# singleboard.net
KiCad netlist of a schematic drawn in EAGLE
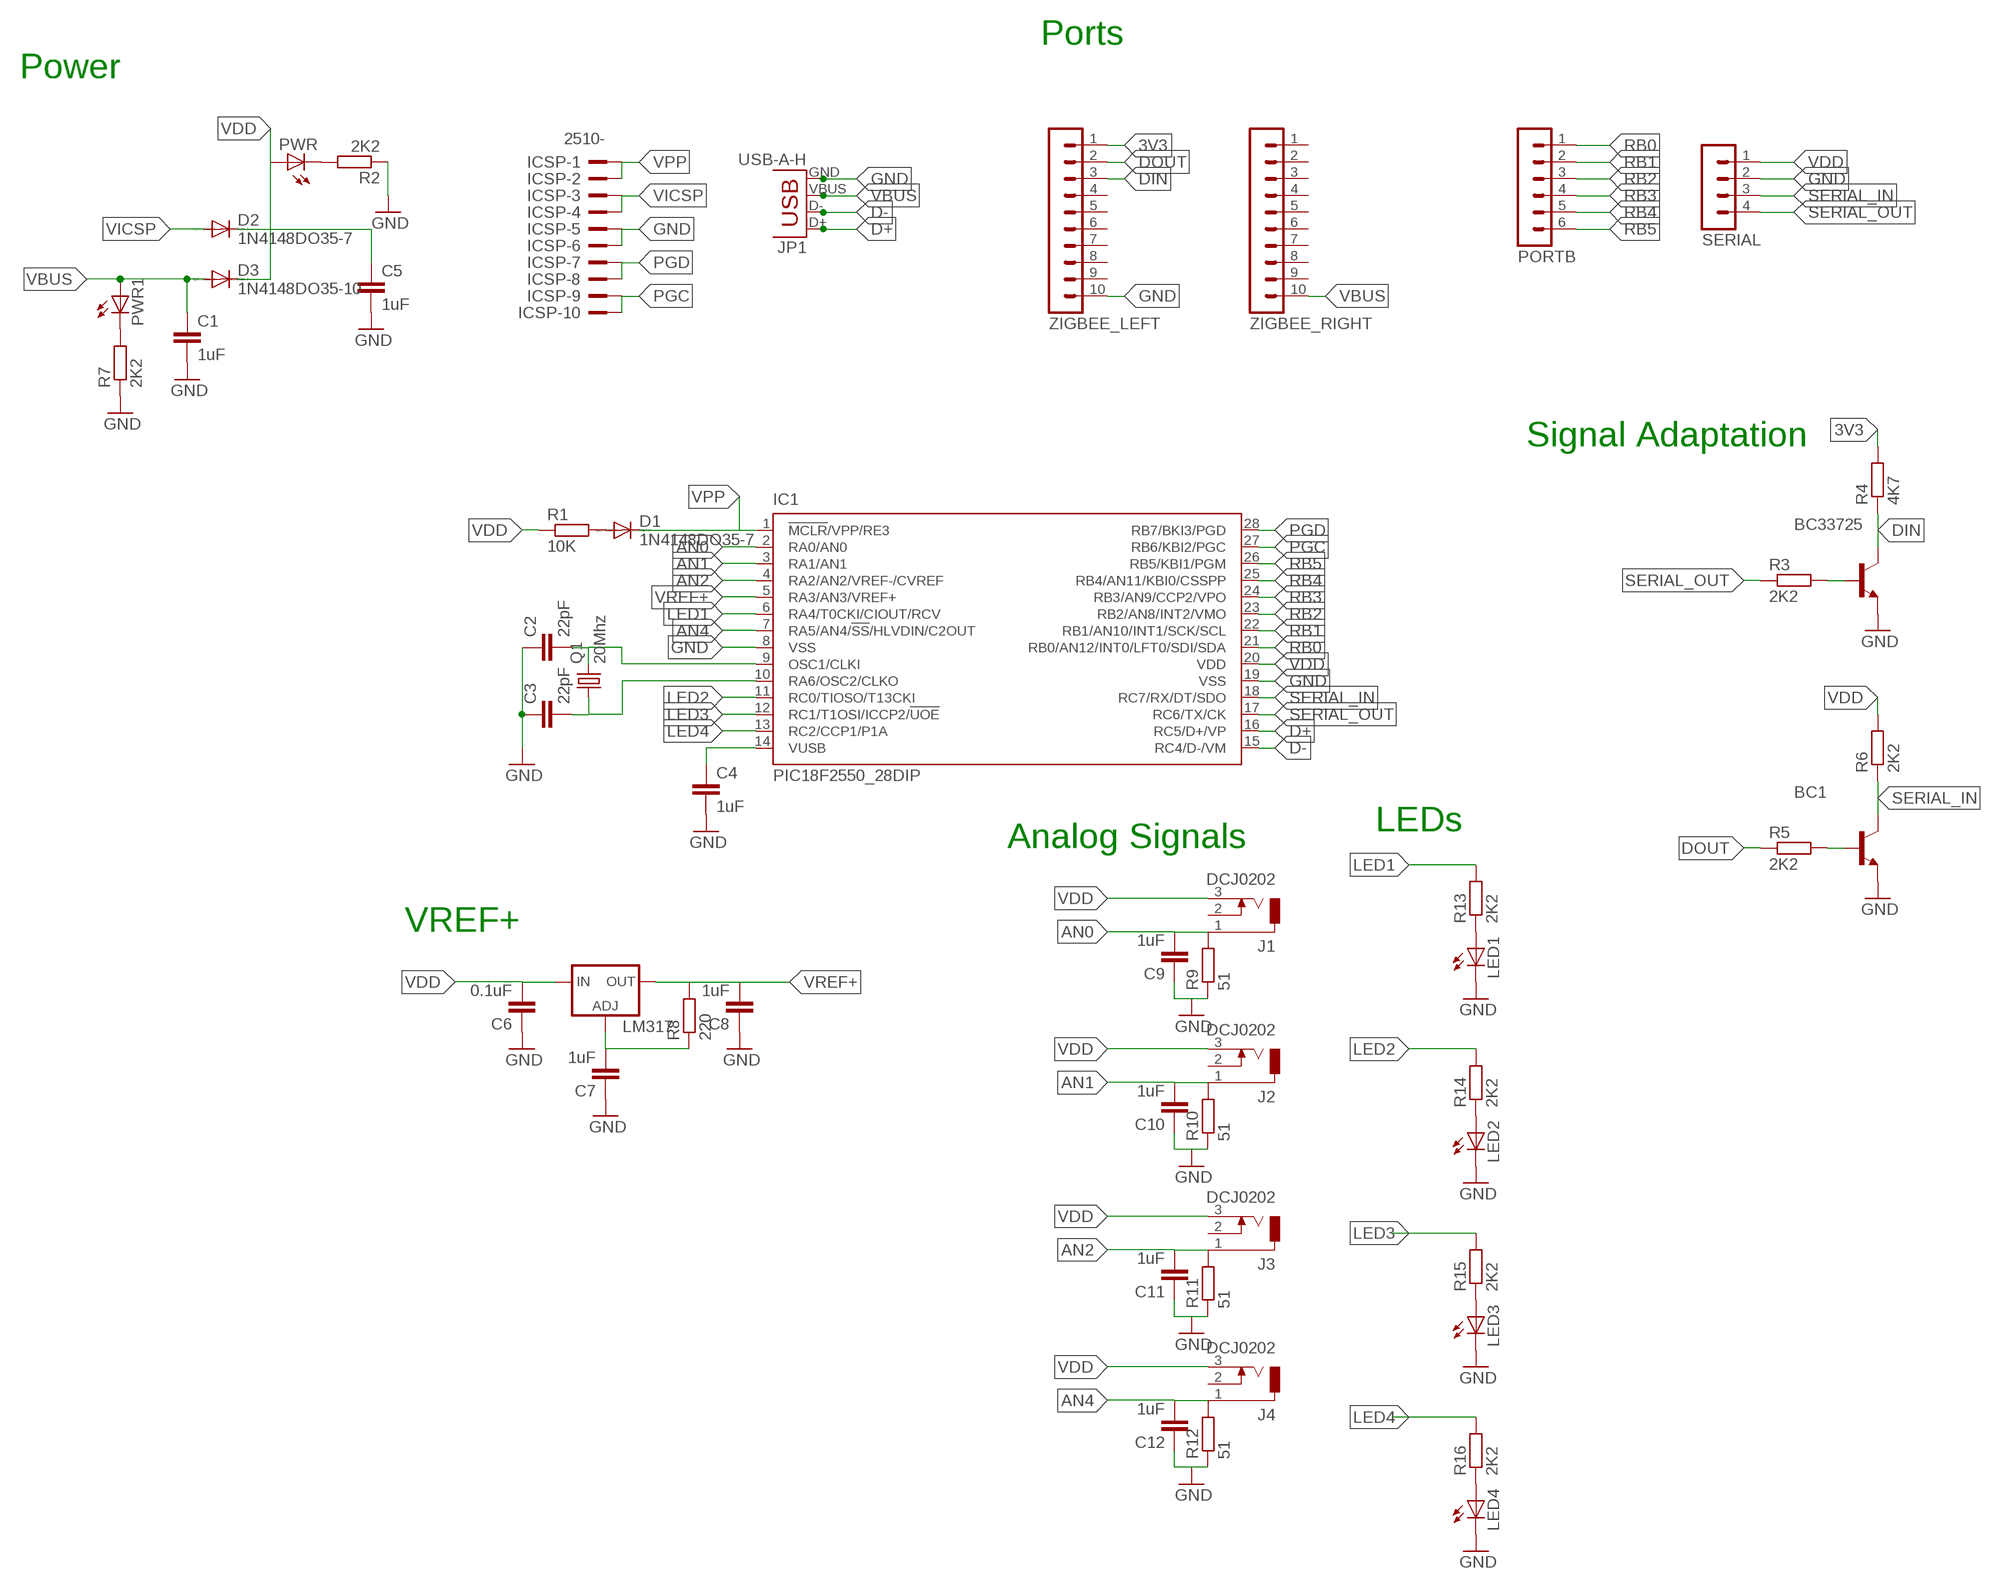
[diagram p0: schematic, sheet 1]

(export (version "E")
  (design (tool "Eeschema 10.0.6"))
  (components
    (comp (ref "BC1")
      (value "BC337-25-NPN-TO92-CBE")
      (footprint "eagle-import:TO92-CBE")
      (libsource (lib "eagle-import") (part "-NPN-TO92-CBEBC337-25"))
    )
    (comp (ref "BC33725")
      (value "BC337-25-NPN-TO92-CBE")
      (footprint "eagle-import:TO92-CBE")
      (libsource (lib "eagle-import") (part "-NPN-TO92-CBEBC337-25"))
    )
    (comp (ref "C1")
      (value "1uF")
      (footprint "eagle-import:C050-025X075")
      (libsource (lib "eagle-import") (part "C-EU050-025X075"))
    )
    (comp (ref "C2")
      (value "22pF")
      (footprint "eagle-import:C025-024X044")
      (libsource (lib "eagle-import") (part "C-EU025-024X044"))
    )
    (comp (ref "C3")
      (value "22pF")
      (footprint "eagle-import:C025-024X044")
      (libsource (lib "eagle-import") (part "C-EU025-024X044"))
    )
    (comp (ref "C4")
      (value "1uF")
      (footprint "eagle-import:C025-024X044")
      (libsource (lib "eagle-import") (part "C-EU025-024X044"))
    )
    (comp (ref "C5")
      (value "1uF")
      (footprint "eagle-import:C025-024X044")
      (libsource (lib "eagle-import") (part "C-EU025-024X044"))
    )
    (comp (ref "C6")
      (value "0.1uF")
      (footprint "eagle-import:C050-025X075")
      (libsource (lib "eagle-import") (part "C-EU050-025X075"))
    )
    (comp (ref "C7")
      (value "1uF")
      (footprint "eagle-import:C050-025X075")
      (libsource (lib "eagle-import") (part "C-EU050-025X075"))
    )
    (comp (ref "C8")
      (value "1uF")
      (footprint "eagle-import:C050-025X075")
      (libsource (lib "eagle-import") (part "C-EU050-025X075"))
    )
    (comp (ref "C9")
      (value "1uF")
      (footprint "eagle-import:C050-025X075")
      (libsource (lib "eagle-import") (part "C-EU050-025X075"))
    )
    (comp (ref "C10")
      (value "1uF")
      (footprint "eagle-import:C050-025X075")
      (libsource (lib "eagle-import") (part "C-EU050-025X075"))
    )
    (comp (ref "C11")
      (value "1uF")
      (footprint "eagle-import:C050-025X075")
      (libsource (lib "eagle-import") (part "C-EU050-025X075"))
    )
    (comp (ref "C12")
      (value "1uF")
      (footprint "eagle-import:C050-025X075")
      (libsource (lib "eagle-import") (part "C-EU050-025X075"))
    )
    (comp (ref "D1")
      (value "1N4148DO35-7")
      (footprint "eagle-import:DO35-7")
      (libsource (lib "eagle-import") (part "1N4148DO35-7"))
    )
    (comp (ref "D2")
      (value "1N4148DO35-7")
      (footprint "eagle-import:DO35-7")
      (libsource (lib "eagle-import") (part "1N4148DO35-7"))
    )
    (comp (ref "D3")
      (value "1N4148DO35-10")
      (footprint "eagle-import:DO35-10")
      (libsource (lib "eagle-import") (part "1N4148DO35-10"))
    )
    (comp (ref "IC1")
      (value "PIC18F2550_28DIP")
      (footprint "eagle-import:DIL28-3")
      (fields (field (name "MF") "MICROCHIP") (field (name "MPN") "PIC18F2550-I/SP"))
      (libsource (lib "eagle-import") (part "PIC18F2_28DIP550"))
    )
    (comp (ref "ICSP")
      (value "2510-")
      (footprint "eagle-import:PAK100_2500-10")
      (fields (field (name "MF") "3M") (field (name "MPN") "2510-6002UB"))
      (libsource (lib "eagle-import") (part "2510-"))
    )
    (comp (ref "J1")
      (value "DCJ0202")
      (footprint "eagle-import:DCJ0202")
      (libsource (lib "eagle-import") (part "DCJ0202"))
    )
    (comp (ref "J2")
      (value "DCJ0202")
      (footprint "eagle-import:DCJ0202")
      (libsource (lib "eagle-import") (part "DCJ0202"))
    )
    (comp (ref "J3")
      (value "DCJ0202")
      (footprint "eagle-import:DCJ0202")
      (libsource (lib "eagle-import") (part "DCJ0202"))
    )
    (comp (ref "J4")
      (value "DCJ0202")
      (footprint "eagle-import:DCJ0202")
      (libsource (lib "eagle-import") (part "DCJ0202"))
    )
    (comp (ref "JP1")
      (value "USB-A-H")
      (footprint "eagle-import:USB-A-H")
      (libsource (lib "eagle-import") (part "USB-A-H"))
    )
    (comp (ref "LED1")
      (value "LED3MM")
      (footprint "eagle-import:LED3MM")
      (libsource (lib "eagle-import") (part "LED3MM"))
    )
    (comp (ref "LED2")
      (value "LED3MM")
      (footprint "eagle-import:LED3MM")
      (libsource (lib "eagle-import") (part "LED3MM"))
    )
    (comp (ref "LED3")
      (value "LED3MM")
      (footprint "eagle-import:LED3MM")
      (libsource (lib "eagle-import") (part "LED3MM"))
    )
    (comp (ref "LED4")
      (value "LED3MM")
      (footprint "eagle-import:LED3MM")
      (libsource (lib "eagle-import") (part "LED3MM"))
    )
    (comp (ref "LM317")
      (value "LM317TS")
      (footprint "eagle-import:317TS")
      (libsource (lib "eagle-import") (part "LM317TS"))
    )
    (comp (ref "PORTB")
      (value "MA06-1")
      (footprint "eagle-import:MA06-1")
      (libsource (lib "eagle-import") (part "MA06-1"))
    )
    (comp (ref "PWR")
      (value "LED3MM")
      (footprint "eagle-import:LED3MM")
      (libsource (lib "eagle-import") (part "LED3MM"))
    )
    (comp (ref "PWR1")
      (value "LED3MM")
      (footprint "eagle-import:LED3MM")
      (libsource (lib "eagle-import") (part "LED3MM"))
    )
    (comp (ref "Q1")
      (value "20Mhz")
      (footprint "eagle-import:HC49_S")
      (libsource (lib "eagle-import") (part "CRYSTALHC49S"))
    )
    (comp (ref "R1")
      (value "10K")
      (footprint "eagle-import:0204_7")
      (libsource (lib "eagle-import") (part "resistor_R-EU_0204/7"))
    )
    (comp (ref "R2")
      (value "2K2")
      (footprint "eagle-import:0204_5")
      (libsource (lib "eagle-import") (part "R-EU_0204/5"))
    )
    (comp (ref "R3")
      (value "2K2")
      (footprint "eagle-import:0204_5")
      (libsource (lib "eagle-import") (part "R-EU_0204/5"))
    )
    (comp (ref "R4")
      (value "4K7")
      (footprint "eagle-import:0204_5")
      (libsource (lib "eagle-import") (part "R-EU_0204/5"))
    )
    (comp (ref "R5")
      (value "2K2")
      (footprint "eagle-import:0204_5")
      (libsource (lib "eagle-import") (part "R-EU_0204/5"))
    )
    (comp (ref "R6")
      (value "2K2")
      (footprint "eagle-import:0204_5")
      (libsource (lib "eagle-import") (part "R-EU_0204/5"))
    )
    (comp (ref "R7")
      (value "2K2")
      (footprint "eagle-import:0204_5")
      (libsource (lib "eagle-import") (part "R-EU_0204/5"))
    )
    (comp (ref "R8")
      (value "220")
      (footprint "eagle-import:0204_5")
      (libsource (lib "eagle-import") (part "R-EU_0204/5"))
    )
    (comp (ref "R9")
      (value "51")
      (footprint "eagle-import:0204_5")
      (libsource (lib "eagle-import") (part "R-EU_0204/5"))
    )
    (comp (ref "R10")
      (value "51")
      (footprint "eagle-import:0204_5")
      (libsource (lib "eagle-import") (part "R-EU_0204/5"))
    )
    (comp (ref "R11")
      (value "51")
      (footprint "eagle-import:0204_5")
      (libsource (lib "eagle-import") (part "R-EU_0204/5"))
    )
    (comp (ref "R12")
      (value "51")
      (footprint "eagle-import:0204_5")
      (libsource (lib "eagle-import") (part "R-EU_0204/5"))
    )
    (comp (ref "R13")
      (value "2K2")
      (footprint "eagle-import:0204_5")
      (libsource (lib "eagle-import") (part "R-EU_0204/5"))
    )
    (comp (ref "R14")
      (value "2K2")
      (footprint "eagle-import:0204_5")
      (libsource (lib "eagle-import") (part "R-EU_0204/5"))
    )
    (comp (ref "R15")
      (value "2K2")
      (footprint "eagle-import:0204_5")
      (libsource (lib "eagle-import") (part "R-EU_0204/5"))
    )
    (comp (ref "R16")
      (value "2K2")
      (footprint "eagle-import:0204_5")
      (libsource (lib "eagle-import") (part "R-EU_0204/5"))
    )
    (comp (ref "SERIAL")
      (value "MA04-1")
      (footprint "eagle-import:MA04-1")
      (libsource (lib "eagle-import") (part "MA04-1"))
    )
    (comp (ref "ZIGBEE_LEFT")
      (value "MA10-1")
      (footprint "eagle-import:MA10-1")
      (libsource (lib "eagle-import") (part "MA10-1"))
    )
    (comp (ref "ZIGBEE_RIGHT")
      (value "MA10-1")
      (footprint "eagle-import:MA10-1")
      (libsource (lib "eagle-import") (part "MA10-1"))
    )
  )
  (nets
    (net (code "1") (name "3V3") (class "Default")
      (node (ref "R4") (pin "2") (pinfunction "2_2") (pintype "passive"))
      (node (ref "ZIGBEE_LEFT") (pin "1") (pinfunction "1_1") (pintype "passive"))
    )
    (net (code "2") (name "AN0") (class "Default")
      (node (ref "C9") (pin "2") (pinfunction "2_2") (pintype "passive"))
      (node (ref "IC1") (pin "2") (pinfunction "RA0/AN0_2") (pintype "bidirectional"))
      (node (ref "J1") (pin "1") (pinfunction "1_1") (pintype "passive"))
      (node (ref "R9") (pin "2") (pinfunction "2_2") (pintype "passive"))
    )
    (net (code "3") (name "AN1") (class "Default")
      (node (ref "C10") (pin "2") (pinfunction "2_2") (pintype "passive"))
      (node (ref "IC1") (pin "3") (pinfunction "RA1/AN1_3") (pintype "bidirectional"))
      (node (ref "J2") (pin "1") (pinfunction "1_1") (pintype "passive"))
      (node (ref "R10") (pin "2") (pinfunction "2_2") (pintype "passive"))
    )
    (net (code "4") (name "AN2") (class "Default")
      (node (ref "C11") (pin "2") (pinfunction "2_2") (pintype "passive"))
      (node (ref "IC1") (pin "4") (pinfunction "RA2/AN2/VREF-/CVREF_4") (pintype "bidirectional"))
      (node (ref "J3") (pin "1") (pinfunction "1_1") (pintype "passive"))
      (node (ref "R11") (pin "2") (pinfunction "2_2") (pintype "passive"))
    )
    (net (code "5") (name "AN4") (class "Default")
      (node (ref "C12") (pin "2") (pinfunction "2_2") (pintype "passive"))
      (node (ref "IC1") (pin "7") (pinfunction "RA5/AN4/~{SS}/HLVDIN/C2OUT_7") (pintype "bidirectional"))
      (node (ref "J4") (pin "1") (pinfunction "1_1") (pintype "passive"))
      (node (ref "R12") (pin "2") (pinfunction "2_2") (pintype "passive"))
    )
    (net (code "6") (name "D+") (class "Default")
      (node (ref "IC1") (pin "16") (pinfunction "RC5/D+/VP_16") (pintype "bidirectional"))
      (node (ref "JP1") (pin "D+") (pinfunction "D+_D+") (pintype "bidirectional"))
    )
    (net (code "7") (name "D-") (class "Default")
      (node (ref "IC1") (pin "15") (pinfunction "RC4/D-/VM_15") (pintype "bidirectional"))
      (node (ref "JP1") (pin "D-") (pinfunction "D-_D-") (pintype "bidirectional"))
    )
    (net (code "8") (name "DIN") (class "Default")
      (node (ref "BC33725") (pin "C") (pinfunction "C_C") (pintype "passive"))
      (node (ref "R4") (pin "1") (pinfunction "1_1") (pintype "passive"))
      (node (ref "ZIGBEE_LEFT") (pin "3") (pinfunction "3_3") (pintype "passive"))
    )
    (net (code "9") (name "DOUT") (class "Default")
      (node (ref "R5") (pin "1") (pinfunction "1_1") (pintype "passive"))
      (node (ref "ZIGBEE_LEFT") (pin "2") (pinfunction "2_2") (pintype "passive"))
    )
    (net (code "10") (name "GND") (class "Default")
      (node (ref "BC1") (pin "E") (pinfunction "E_E") (pintype "passive"))
      (node (ref "BC33725") (pin "E") (pinfunction "E_E") (pintype "passive"))
      (node (ref "C1") (pin "2") (pinfunction "2_2") (pintype "passive"))
      (node (ref "C10") (pin "1") (pinfunction "1_1") (pintype "passive"))
      (node (ref "C11") (pin "1") (pinfunction "1_1") (pintype "passive"))
      (node (ref "C12") (pin "1") (pinfunction "1_1") (pintype "passive"))
      (node (ref "C2") (pin "1") (pinfunction "1_1") (pintype "passive"))
      (node (ref "C3") (pin "1") (pinfunction "1_1") (pintype "passive"))
      (node (ref "C4") (pin "2") (pinfunction "2_2") (pintype "passive"))
      (node (ref "C5") (pin "2") (pinfunction "2_2") (pintype "passive"))
      (node (ref "C6") (pin "1") (pinfunction "1_1") (pintype "passive"))
      (node (ref "C7") (pin "1") (pinfunction "1_1") (pintype "passive"))
      (node (ref "C8") (pin "1") (pinfunction "1_1") (pintype "passive"))
      (node (ref "C9") (pin "1") (pinfunction "1_1") (pintype "passive"))
      (node (ref "IC1") (pin "19") (pinfunction "VSS_19") (pintype "power_in"))
      (node (ref "IC1") (pin "8") (pinfunction "VSS_8") (pintype "power_in"))
      (node (ref "ICSP") (pin "5") (pinfunction "KL_5") (pintype "passive"))
      (node (ref "ICSP") (pin "6") (pinfunction "KL_6") (pintype "passive"))
      (node (ref "JP1") (pin "GND") (pinfunction "GND_GND") (pintype "bidirectional"))
      (node (ref "LED1") (pin "K") (pinfunction "C_K") (pintype "passive"))
      (node (ref "LED2") (pin "K") (pinfunction "C_K") (pintype "passive"))
      (node (ref "LED3") (pin "K") (pinfunction "C_K") (pintype "passive"))
      (node (ref "LED4") (pin "K") (pinfunction "C_K") (pintype "passive"))
      (node (ref "R10") (pin "1") (pinfunction "1_1") (pintype "passive"))
      (node (ref "R11") (pin "1") (pinfunction "1_1") (pintype "passive"))
      (node (ref "R12") (pin "1") (pinfunction "1_1") (pintype "passive"))
      (node (ref "R2") (pin "1") (pinfunction "1_1") (pintype "passive"))
      (node (ref "R7") (pin "1") (pinfunction "1_1") (pintype "passive"))
      (node (ref "R9") (pin "1") (pinfunction "1_1") (pintype "passive"))
      (node (ref "SERIAL") (pin "2") (pinfunction "2_2") (pintype "passive"))
      (node (ref "ZIGBEE_LEFT") (pin "10") (pinfunction "10_10") (pintype "passive"))
    )
    (net (code "11") (name "LED1") (class "Default")
      (node (ref "IC1") (pin "6") (pinfunction "RA4/T0CKI/CIOUT/RCV_6") (pintype "bidirectional"))
      (node (ref "R13") (pin "2") (pinfunction "2_2") (pintype "passive"))
    )
    (net (code "12") (name "LED2") (class "Default")
      (node (ref "IC1") (pin "11") (pinfunction "RC0/TIOSO/T13CKI_11") (pintype "bidirectional"))
      (node (ref "R14") (pin "2") (pinfunction "2_2") (pintype "passive"))
    )
    (net (code "13") (name "LED3") (class "Default")
      (node (ref "IC1") (pin "12") (pinfunction "RC1/T1OSI/ICCP2/~{UOE}_12") (pintype "bidirectional"))
      (node (ref "R15") (pin "2") (pinfunction "2_2") (pintype "passive"))
    )
    (net (code "14") (name "LED4") (class "Default")
      (node (ref "IC1") (pin "13") (pinfunction "RC2/CCP1/P1A_13") (pintype "bidirectional"))
      (node (ref "R16") (pin "2") (pinfunction "2_2") (pintype "passive"))
    )
    (net (code "15") (name "Net-(BC1-PadB)") (class "Default")
      (node (ref "BC1") (pin "B") (pinfunction "B_B") (pintype "passive"))
      (node (ref "R5") (pin "2") (pinfunction "2_2") (pintype "passive"))
    )
    (net (code "16") (name "Net-(BC33725-PadB)") (class "Default")
      (node (ref "BC33725") (pin "B") (pinfunction "B_B") (pintype "passive"))
      (node (ref "R3") (pin "2") (pinfunction "2_2") (pintype "passive"))
    )
    (net (code "17") (name "Net-(D1-PadA)") (class "Default")
      (node (ref "D1") (pin "A") (pinfunction "A_A") (pintype "passive"))
      (node (ref "R1") (pin "2") (pinfunction "2_2") (pintype "passive"))
    )
    (net (code "18") (name "Net-(IC1-OSC1{slash}CLKI)") (class "Default")
      (node (ref "C2") (pin "2") (pinfunction "2_2") (pintype "passive"))
      (node (ref "IC1") (pin "9") (pinfunction "OSC1/CLKI_9") (pintype "input"))
      (node (ref "Q1") (pin "2") (pinfunction "2_2") (pintype "passive"))
    )
    (net (code "19") (name "Net-(IC1-RA6{slash}OSC2{slash}CLKO)") (class "Default")
      (node (ref "C3") (pin "2") (pinfunction "2_2") (pintype "passive"))
      (node (ref "IC1") (pin "10") (pinfunction "RA6/OSC2/CLKO_10") (pintype "output"))
      (node (ref "Q1") (pin "1") (pinfunction "1_1") (pintype "passive"))
    )
    (net (code "20") (name "Net-(IC1-VUSB)") (class "Default")
      (node (ref "C4") (pin "1") (pinfunction "1_1") (pintype "passive"))
      (node (ref "IC1") (pin "14") (pinfunction "VUSB_14") (pintype "bidirectional"))
    )
    (net (code "21") (name "Net-(LED1-PadA)") (class "Default")
      (node (ref "LED1") (pin "A") (pinfunction "A_A") (pintype "passive"))
      (node (ref "R13") (pin "1") (pinfunction "1_1") (pintype "passive"))
    )
    (net (code "22") (name "Net-(LED2-PadA)") (class "Default")
      (node (ref "LED2") (pin "A") (pinfunction "A_A") (pintype "passive"))
      (node (ref "R14") (pin "1") (pinfunction "1_1") (pintype "passive"))
    )
    (net (code "23") (name "Net-(LED3-PadA)") (class "Default")
      (node (ref "LED3") (pin "A") (pinfunction "A_A") (pintype "passive"))
      (node (ref "R15") (pin "1") (pinfunction "1_1") (pintype "passive"))
    )
    (net (code "24") (name "Net-(LED4-PadA)") (class "Default")
      (node (ref "LED4") (pin "A") (pinfunction "A_A") (pintype "passive"))
      (node (ref "R16") (pin "1") (pinfunction "1_1") (pintype "passive"))
    )
    (net (code "25") (name "Net-(LM317-ADJ)") (class "Default")
      (node (ref "C7") (pin "2") (pinfunction "2_2") (pintype "passive"))
      (node (ref "LM317") (pin "1") (pinfunction "ADJ_1") (pintype "input"))
      (node (ref "R8") (pin "1") (pinfunction "1_1") (pintype "passive"))
    )
    (net (code "26") (name "Net-(PWR-C)") (class "Default")
      (node (ref "PWR") (pin "K") (pinfunction "C_K") (pintype "passive"))
      (node (ref "R2") (pin "2") (pinfunction "2_2") (pintype "passive"))
    )
    (net (code "27") (name "Net-(PWR1-C)") (class "Default")
      (node (ref "PWR1") (pin "K") (pinfunction "C_K") (pintype "passive"))
      (node (ref "R7") (pin "2") (pinfunction "2_2") (pintype "passive"))
    )
    (net (code "28") (name "PGC") (class "Default")
      (node (ref "IC1") (pin "27") (pinfunction "RB6/KBI2/PGC_27") (pintype "bidirectional"))
      (node (ref "ICSP") (pin "10") (pinfunction "KL_10") (pintype "passive"))
      (node (ref "ICSP") (pin "9") (pinfunction "KL_9") (pintype "passive"))
    )
    (net (code "29") (name "PGD") (class "Default")
      (node (ref "IC1") (pin "28") (pinfunction "RB7/BKI3/PGD_28") (pintype "bidirectional"))
      (node (ref "ICSP") (pin "7") (pinfunction "KL_7") (pintype "passive"))
      (node (ref "ICSP") (pin "8") (pinfunction "KL_8") (pintype "passive"))
    )
    (net (code "30") (name "RB0") (class "Default")
      (node (ref "IC1") (pin "21") (pinfunction "RB0/AN12/INT0/LFT0/SDI/SDA_21") (pintype "bidirectional"))
      (node (ref "PORTB") (pin "1") (pinfunction "1_1") (pintype "passive"))
    )
    (net (code "31") (name "RB1") (class "Default")
      (node (ref "IC1") (pin "22") (pinfunction "RB1/AN10/INT1/SCK/SCL_22") (pintype "bidirectional"))
      (node (ref "PORTB") (pin "2") (pinfunction "2_2") (pintype "passive"))
    )
    (net (code "32") (name "RB2") (class "Default")
      (node (ref "IC1") (pin "23") (pinfunction "RB2/AN8/INT2/VMO_23") (pintype "bidirectional"))
      (node (ref "PORTB") (pin "3") (pinfunction "3_3") (pintype "passive"))
    )
    (net (code "33") (name "RB3") (class "Default")
      (node (ref "IC1") (pin "24") (pinfunction "RB3/AN9/CCP2/VPO_24") (pintype "bidirectional"))
      (node (ref "PORTB") (pin "4") (pinfunction "4_4") (pintype "passive"))
    )
    (net (code "34") (name "RB4") (class "Default")
      (node (ref "IC1") (pin "25") (pinfunction "RB4/AN11/KBI0/CSSPP_25") (pintype "bidirectional"))
      (node (ref "PORTB") (pin "5") (pinfunction "5_5") (pintype "passive"))
    )
    (net (code "35") (name "RB5") (class "Default")
      (node (ref "IC1") (pin "26") (pinfunction "RB5/KBI1/PGM_26") (pintype "bidirectional"))
      (node (ref "PORTB") (pin "6") (pinfunction "6_6") (pintype "passive"))
    )
    (net (code "36") (name "SERIAL_IN") (class "Default")
      (node (ref "BC1") (pin "C") (pinfunction "C_C") (pintype "passive"))
      (node (ref "IC1") (pin "18") (pinfunction "RC7/RX/DT/SDO_18") (pintype "bidirectional"))
      (node (ref "R6") (pin "1") (pinfunction "1_1") (pintype "passive"))
      (node (ref "SERIAL") (pin "3") (pinfunction "3_3") (pintype "passive"))
    )
    (net (code "37") (name "SERIAL_OUT") (class "Default")
      (node (ref "IC1") (pin "17") (pinfunction "RC6/TX/CK_17") (pintype "bidirectional"))
      (node (ref "R3") (pin "1") (pinfunction "1_1") (pintype "passive"))
      (node (ref "SERIAL") (pin "4") (pinfunction "4_4") (pintype "passive"))
    )
    (net (code "38") (name "VBUS") (class "Default")
      (node (ref "C1") (pin "1") (pinfunction "1_1") (pintype "passive"))
      (node (ref "D3") (pin "A") (pinfunction "A_A") (pintype "passive"))
      (node (ref "JP1") (pin "VBUS") (pinfunction "VBUS_VBUS") (pintype "bidirectional"))
      (node (ref "PWR1") (pin "A") (pinfunction "A_A") (pintype "passive"))
      (node (ref "ZIGBEE_RIGHT") (pin "10") (pinfunction "10_10") (pintype "passive"))
    )
    (net (code "39") (name "VDD") (class "Default")
      (node (ref "C5") (pin "1") (pinfunction "1_1") (pintype "passive"))
      (node (ref "C6") (pin "2") (pinfunction "2_2") (pintype "passive"))
      (node (ref "D2") (pin "C") (pinfunction "C_C") (pintype "passive"))
      (node (ref "D3") (pin "C") (pinfunction "C_C") (pintype "passive"))
      (node (ref "IC1") (pin "20") (pinfunction "VDD_20") (pintype "power_in"))
      (node (ref "J1") (pin "3") (pinfunction "3_3") (pintype "passive"))
      (node (ref "J2") (pin "3") (pinfunction "3_3") (pintype "passive"))
      (node (ref "J3") (pin "3") (pinfunction "3_3") (pintype "passive"))
      (node (ref "J4") (pin "3") (pinfunction "3_3") (pintype "passive"))
      (node (ref "LM317") (pin "3") (pinfunction "IN_3") (pintype "input"))
      (node (ref "PWR") (pin "A") (pinfunction "A_A") (pintype "passive"))
      (node (ref "R1") (pin "1") (pinfunction "1_1") (pintype "passive"))
      (node (ref "R6") (pin "2") (pinfunction "2_2") (pintype "passive"))
      (node (ref "SERIAL") (pin "1") (pinfunction "1_1") (pintype "passive"))
    )
    (net (code "40") (name "VICSP") (class "Default")
      (node (ref "D2") (pin "A") (pinfunction "A_A") (pintype "passive"))
      (node (ref "ICSP") (pin "3") (pinfunction "KL_3") (pintype "passive"))
      (node (ref "ICSP") (pin "4") (pinfunction "KL_4") (pintype "passive"))
    )
    (net (code "41") (name "VPP") (class "Default")
      (node (ref "D1") (pin "C") (pinfunction "C_C") (pintype "passive"))
      (node (ref "IC1") (pin "1") (pinfunction "~{MCLR}/VPP/RE3_1") (pintype "input"))
      (node (ref "ICSP") (pin "1") (pinfunction "KL_1") (pintype "passive"))
      (node (ref "ICSP") (pin "2") (pinfunction "KL_2") (pintype "passive"))
    )
    (net (code "42") (name "VREF+") (class "Default")
      (node (ref "C8") (pin "2") (pinfunction "2_2") (pintype "passive"))
      (node (ref "IC1") (pin "5") (pinfunction "RA3/AN3/VREF+_5") (pintype "bidirectional"))
      (node (ref "LM317") (pin "2") (pinfunction "OUT_2") (pintype "passive"))
      (node (ref "R8") (pin "2") (pinfunction "2_2") (pintype "passive"))
    )
    (net (code "43") (name "unconnected-(J1-Pad2)") (class "Default")
      (node (ref "J1") (pin "2") (pinfunction "2_2") (pintype "passive"))
    )
    (net (code "44") (name "unconnected-(J2-Pad2)") (class "Default")
      (node (ref "J2") (pin "2") (pinfunction "2_2") (pintype "passive"))
    )
    (net (code "45") (name "unconnected-(J3-Pad2)") (class "Default")
      (node (ref "J3") (pin "2") (pinfunction "2_2") (pintype "passive"))
    )
    (net (code "46") (name "unconnected-(J4-Pad2)") (class "Default")
      (node (ref "J4") (pin "2") (pinfunction "2_2") (pintype "passive"))
    )
    (net (code "47") (name "unconnected-(ZIGBEE_LEFT-Pad4)") (class "Default")
      (node (ref "ZIGBEE_LEFT") (pin "4") (pinfunction "4_4") (pintype "passive"))
    )
    (net (code "48") (name "unconnected-(ZIGBEE_LEFT-Pad5)") (class "Default")
      (node (ref "ZIGBEE_LEFT") (pin "5") (pinfunction "5_5") (pintype "passive"))
    )
    (net (code "49") (name "unconnected-(ZIGBEE_LEFT-Pad6)") (class "Default")
      (node (ref "ZIGBEE_LEFT") (pin "6") (pinfunction "6_6") (pintype "passive"))
    )
    (net (code "50") (name "unconnected-(ZIGBEE_LEFT-Pad7)") (class "Default")
      (node (ref "ZIGBEE_LEFT") (pin "7") (pinfunction "7_7") (pintype "passive"))
    )
    (net (code "51") (name "unconnected-(ZIGBEE_LEFT-Pad8)") (class "Default")
      (node (ref "ZIGBEE_LEFT") (pin "8") (pinfunction "8_8") (pintype "passive"))
    )
    (net (code "52") (name "unconnected-(ZIGBEE_LEFT-Pad9)") (class "Default")
      (node (ref "ZIGBEE_LEFT") (pin "9") (pinfunction "9_9") (pintype "passive"))
    )
    (net (code "53") (name "unconnected-(ZIGBEE_RIGHT-Pad1)") (class "Default")
      (node (ref "ZIGBEE_RIGHT") (pin "1") (pinfunction "1_1") (pintype "passive"))
    )
    (net (code "54") (name "unconnected-(ZIGBEE_RIGHT-Pad2)") (class "Default")
      (node (ref "ZIGBEE_RIGHT") (pin "2") (pinfunction "2_2") (pintype "passive"))
    )
    (net (code "55") (name "unconnected-(ZIGBEE_RIGHT-Pad3)") (class "Default")
      (node (ref "ZIGBEE_RIGHT") (pin "3") (pinfunction "3_3") (pintype "passive"))
    )
    (net (code "56") (name "unconnected-(ZIGBEE_RIGHT-Pad4)") (class "Default")
      (node (ref "ZIGBEE_RIGHT") (pin "4") (pinfunction "4_4") (pintype "passive"))
    )
    (net (code "57") (name "unconnected-(ZIGBEE_RIGHT-Pad5)") (class "Default")
      (node (ref "ZIGBEE_RIGHT") (pin "5") (pinfunction "5_5") (pintype "passive"))
    )
    (net (code "58") (name "unconnected-(ZIGBEE_RIGHT-Pad6)") (class "Default")
      (node (ref "ZIGBEE_RIGHT") (pin "6") (pinfunction "6_6") (pintype "passive"))
    )
    (net (code "59") (name "unconnected-(ZIGBEE_RIGHT-Pad7)") (class "Default")
      (node (ref "ZIGBEE_RIGHT") (pin "7") (pinfunction "7_7") (pintype "passive"))
    )
    (net (code "60") (name "unconnected-(ZIGBEE_RIGHT-Pad8)") (class "Default")
      (node (ref "ZIGBEE_RIGHT") (pin "8") (pinfunction "8_8") (pintype "passive"))
    )
    (net (code "61") (name "unconnected-(ZIGBEE_RIGHT-Pad9)") (class "Default")
      (node (ref "ZIGBEE_RIGHT") (pin "9") (pinfunction "9_9") (pintype "passive"))
    )
  )
)
